# Inputs.net
KiCad netlist of a schematic drawn in Altium Designer
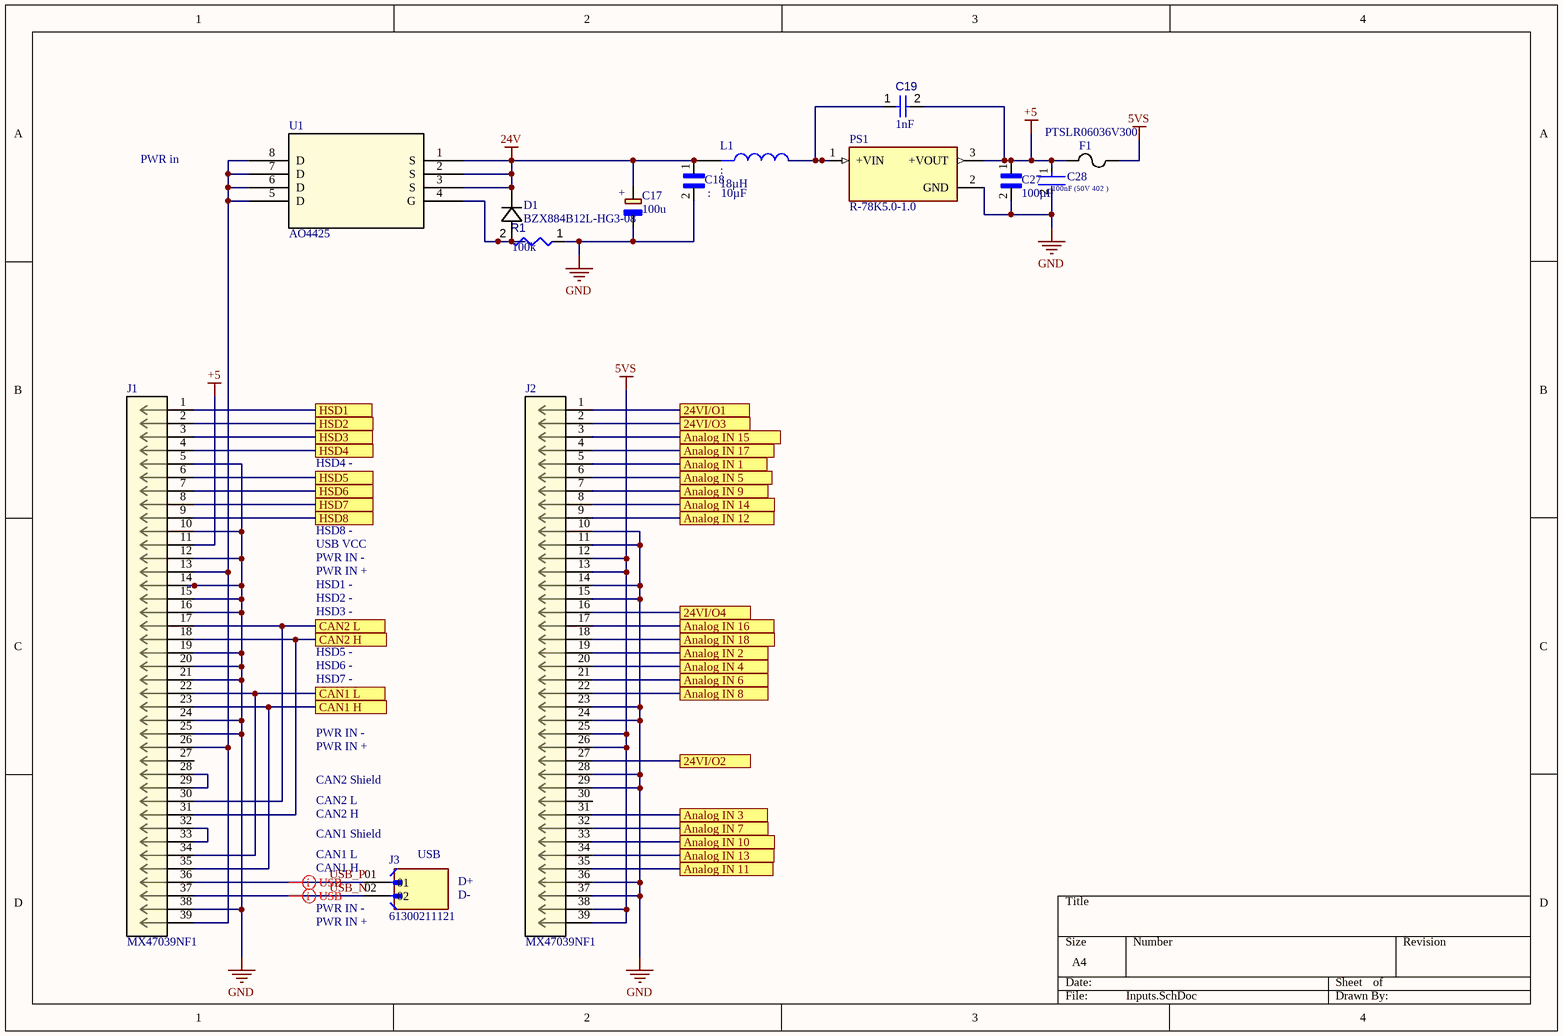
[diagram p0: Inputs.SchDoc]

(export (version "E")
  (design (tool "Eeschema 10.0.6"))
  (components
    (comp (ref "C17")
      (value "100u")
      (footprint "865080445010")
      (description "100 ÂµF 35 V Aluminum Electrolytic Capacitors Radial, Can - SMD - 2000 Hrs @ 105Â°C")
      (fields (field (name "MF") "WÃ¼rth Elektronik") (field (name "MP") "865080545012"))
      (libsource (lib "Western Formula Racing") (part "865080545012"))
    )
    (comp (ref "C18")
      (value "10µF")
      (footprint "CAPC2012X145N")
      (description "SMD capacitor X5R(EIA) with capacitance 10uF Tol.10%. Rated voltage 50Vdc 85C")
      (fields (field (name "MP") "GRM21BR61H106KE43L") (field (name "MF") "Murata Electronics"))
      (libsource (lib "Western Formula Racing") (part "GRM21BR61H106KE43L"))
    )
    (comp (ref "C19")
      (value "1nF")
      (footprint "CAPC0402(1005)33_L")
      (description "Chip Capacitor, 1nF +/-20%, 50V, 0402, Thickness 0.33 mm")
      (fields (field (name "TOLERANCE") "10%") (field (name "Comment") "Capacitor 1nF +/-20% 50V 0402"))
      (libsource (lib "Western Formula Racing") (part "CAP-NP-2"))
    )
    (comp (ref "C27")
      (value "100µF")
      (footprint "CAPC3216X190N")
      (fields (field (name "MP") "GRM31CR61A107MEA8L"))
      (libsource (lib "Western Formula Racing") (part "GRM31CR61A107MEA8L"))
    )
    (comp (ref "C28")
      (value "100nF (50V 402 )")
      (footprint "FP-CL779-IPC_C")
      (description "Cap Ceramic 100nF 50V X7R ±10% SMD 0402 +125°C Paper T/R")
      (libsource (lib "Altium Content Vault") (part "b4654b650e69147ec39a6b967a45e02"))
    )
    (comp (ref "D1")
      (value "BZX884B12L-HG3-08")
      (footprint "CR_9V1L-HG3-08_VIS")
      (description "No Description Available")
      (fields (field (name "COPYRIGHT") "Copyright (C) 2023 Ultra Librarian. All rights reserved."))
      (libsource (lib "Western Formula Racing") (part "BZX884B12L-HG3-08"))
    )
    (comp (ref "F1")
      (value "PTSLR06036V300")
      (footprint "FUSE_PTSLR06036V300_EAT")
      (description "No Description Available")
      (fields (field (name "COPYRIGHT") "Copyright (C) 2023 Ultra Librarian. All rights reserved."))
      (libsource (lib "Western Formula Racing") (part "PTSLR06036V300"))
    )
    (comp (ref "J1")
      (value "MX47039NF1")
      (footprint "CONN39_MX47039_JAE")
      (description "No Description Available")
      (fields (field (name "COPYRIGHT") "Copyright (C) 2023 Ultra Librarian. All rights reserved."))
      (libsource (lib "Western Formula Racing") (part "MX47039NF1"))
    )
    (comp (ref "J2")
      (value "MX47039NF1")
      (footprint "CONN39_MX47039_JAE")
      (description "No Description Available")
      (fields (field (name "COPYRIGHT") "Copyright (C) 2023 Ultra Librarian. All rights reserved."))
      (libsource (lib "Western Formula Racing") (part "MX47039NF1"))
    )
    (comp (ref "J3")
      (value "61300211121")
      (footprint "WURTH_61300211121")
      (description "Connector Header Through Hole 2 position 0.100 (2.54mm)")
      (fields (field (name "MF") "Wurth Electronics"))
      (libsource (lib "Western Formula Racing") (part "61300211121"))
    )
    (comp (ref "L1")
      (value "18µH")
      (footprint "IND_RLS-186")
      (description "Line Inductors for RECOM Power Supply")
      (fields (field (name "MP") "RLS-186") (field (name "MF") "Recom Power"))
      (libsource (lib "Western Formula Racing") (part "RLS-186"))
    )
    (comp (ref "PS1")
      (value "R-78K5.0-1.0")
      (footprint "CONV_R-78K5.0-1.0")
      (description "1A DC/DC-Converter 'INNOLINE' SIP3 reg")
      (fields (field (name "MF") "Recom Power"))
      (libsource (lib "Western Formula Racing") (part "R-78K5.0-1.0"))
    )
    (comp (ref "R1")
      (value "100k")
      (footprint "RESC0402(1005)_L")
      (description "Chip Resistor, 100 kOhms, +/-1 %, 63 mW, -55 to 155 degC, 0402")
      (fields (field (name "TOLERANCE") "1%") (field (name "POWER") "63mW"))
      (libsource (lib "Western Formula Racing") (part "RES-2"))
    )
    (comp (ref "U1")
      (value "AO4425")
      (footprint "SO-8_AOS")
      (description "No Description Available")
      (fields (field (name "COPYRIGHT") "Copyright (C) 2023 Ultra Librarian. All rights reserved."))
      (libsource (lib "Western Formula Racing") (part "AO4286"))
    )
  )
  (nets
    (net (code "1") (name "+5") (class "Default")
      (node (ref "C19") (pin "2") (pinfunction "2_2") (pintype "passive"))
      (node (ref "C27") (pin "1") (pinfunction "1_1") (pintype "passive"))
      (node (ref "C28") (pin "1") (pinfunction "1_1") (pintype "passive"))
      (node (ref "F1") (pin "1") (pinfunction "1_1") (pintype "passive"))
      (node (ref "J1") (pin "11") (pinfunction "11_11") (pintype "passive"))
      (node (ref "PS1") (pin "3") (pinfunction "+VOUT_3") (pintype "output"))
    )
    (net (code "2") (name "/24VI{slash}O1") (class "Default")
      (node (ref "J2") (pin "1") (pinfunction "1_1") (pintype "passive"))
    )
    (net (code "3") (name "/24VI{slash}O2") (class "Default")
      (node (ref "J2") (pin "27") (pinfunction "27_27") (pintype "passive"))
    )
    (net (code "4") (name "/24VI{slash}O3") (class "Default")
      (node (ref "J2") (pin "2") (pinfunction "2_2") (pintype "passive"))
    )
    (net (code "5") (name "/24VI{slash}O4") (class "Default")
      (node (ref "J2") (pin "16") (pinfunction "16_16") (pintype "passive"))
    )
    (net (code "6") (name "/Analog IN 1") (class "Default")
      (node (ref "J2") (pin "5") (pinfunction "5_5") (pintype "passive"))
    )
    (net (code "7") (name "/Analog IN 2") (class "Default")
      (node (ref "J2") (pin "19") (pinfunction "19_19") (pintype "passive"))
    )
    (net (code "8") (name "/Analog IN 3") (class "Default")
      (node (ref "J2") (pin "31") (pinfunction "31_31") (pintype "passive"))
    )
    (net (code "9") (name "/Analog IN 4") (class "Default")
      (node (ref "J2") (pin "20") (pinfunction "20_20") (pintype "passive"))
    )
    (net (code "10") (name "/Analog IN 5") (class "Default")
      (node (ref "J2") (pin "6") (pinfunction "6_6") (pintype "passive"))
    )
    (net (code "11") (name "/Analog IN 6") (class "Default")
      (node (ref "J2") (pin "21") (pinfunction "21_21") (pintype "passive"))
    )
    (net (code "12") (name "/Analog IN 7") (class "Default")
      (node (ref "J2") (pin "32") (pinfunction "32_32") (pintype "passive"))
    )
    (net (code "13") (name "/Analog IN 8") (class "Default")
      (node (ref "J2") (pin "22") (pinfunction "22_22") (pintype "passive"))
    )
    (net (code "14") (name "/Analog IN 9") (class "Default")
      (node (ref "J2") (pin "7") (pinfunction "7_7") (pintype "passive"))
    )
    (net (code "15") (name "/Analog IN 10") (class "Default")
      (node (ref "J2") (pin "33") (pinfunction "33_33") (pintype "passive"))
    )
    (net (code "16") (name "/Analog IN 11") (class "Default")
      (node (ref "J2") (pin "35") (pinfunction "35_35") (pintype "passive"))
    )
    (net (code "17") (name "/Analog IN 12") (class "Default")
      (node (ref "J2") (pin "9") (pinfunction "9_9") (pintype "passive"))
    )
    (net (code "18") (name "/Analog IN 13") (class "Default")
      (node (ref "J2") (pin "34") (pinfunction "34_34") (pintype "passive"))
    )
    (net (code "19") (name "/Analog IN 14") (class "Default")
      (node (ref "J2") (pin "8") (pinfunction "8_8") (pintype "passive"))
    )
    (net (code "20") (name "/Analog IN 15") (class "Default")
      (node (ref "J2") (pin "3") (pinfunction "3_3") (pintype "passive"))
    )
    (net (code "21") (name "/Analog IN 16") (class "Default")
      (node (ref "J2") (pin "17") (pinfunction "17_17") (pintype "passive"))
    )
    (net (code "22") (name "/Analog IN 17") (class "Default")
      (node (ref "J2") (pin "4") (pinfunction "4_4") (pintype "passive"))
    )
    (net (code "23") (name "/Analog IN 18") (class "Default")
      (node (ref "J2") (pin "18") (pinfunction "18_18") (pintype "passive"))
    )
    (net (code "24") (name "/CAN1 H") (class "Default")
      (node (ref "J1") (pin "23") (pinfunction "23_23") (pintype "passive"))
      (node (ref "J1") (pin "35") (pinfunction "35_35") (pintype "passive"))
    )
    (net (code "25") (name "/CAN1 L") (class "Default")
      (node (ref "J1") (pin "22") (pinfunction "22_22") (pintype "passive"))
      (node (ref "J1") (pin "34") (pinfunction "34_34") (pintype "passive"))
    )
    (net (code "26") (name "/CAN2 H") (class "Default")
      (node (ref "J1") (pin "18") (pinfunction "18_18") (pintype "passive"))
      (node (ref "J1") (pin "31") (pinfunction "31_31") (pintype "passive"))
    )
    (net (code "27") (name "/CAN2 L") (class "Default")
      (node (ref "J1") (pin "17") (pinfunction "17_17") (pintype "passive"))
      (node (ref "J1") (pin "30") (pinfunction "30_30") (pintype "passive"))
    )
    (net (code "28") (name "/HSD1") (class "Default")
      (node (ref "J1") (pin "1") (pinfunction "1_1") (pintype "passive"))
    )
    (net (code "29") (name "/HSD2") (class "Default")
      (node (ref "J1") (pin "2") (pinfunction "2_2") (pintype "passive"))
    )
    (net (code "30") (name "/HSD3") (class "Default")
      (node (ref "J1") (pin "3") (pinfunction "3_3") (pintype "passive"))
    )
    (net (code "31") (name "/HSD4") (class "Default")
      (node (ref "J1") (pin "4") (pinfunction "4_4") (pintype "passive"))
    )
    (net (code "32") (name "/HSD5") (class "Default")
      (node (ref "J1") (pin "6") (pinfunction "6_6") (pintype "passive"))
    )
    (net (code "33") (name "/HSD6") (class "Default")
      (node (ref "J1") (pin "7") (pinfunction "7_7") (pintype "passive"))
    )
    (net (code "34") (name "/HSD7") (class "Default")
      (node (ref "J1") (pin "8") (pinfunction "8_8") (pintype "passive"))
    )
    (net (code "35") (name "/HSD8") (class "Default")
      (node (ref "J1") (pin "9") (pinfunction "9_9") (pintype "passive"))
    )
    (net (code "36") (name "/USB_N") (class "Default")
      (node (ref "J1") (pin "37") (pinfunction "37_37") (pintype "passive"))
      (node (ref "J3") (pin "02") (pinfunction "02_02") (pintype "passive"))
    )
    (net (code "37") (name "/USB_P") (class "Default")
      (node (ref "J1") (pin "36") (pinfunction "36_36") (pintype "passive"))
      (node (ref "J3") (pin "01") (pinfunction "01_01") (pintype "passive"))
    )
    (net (code "38") (name "5VS") (class "Default")
      (node (ref "F1") (pin "2") (pinfunction "2_2") (pintype "passive"))
      (node (ref "J2") (pin "12") (pinfunction "12_12") (pintype "passive"))
      (node (ref "J2") (pin "13") (pinfunction "13_13") (pintype "passive"))
      (node (ref "J2") (pin "25") (pinfunction "25_25") (pintype "passive"))
      (node (ref "J2") (pin "26") (pinfunction "26_26") (pintype "passive"))
      (node (ref "J2") (pin "38") (pinfunction "38_38") (pintype "passive"))
      (node (ref "J2") (pin "39") (pinfunction "39_39") (pintype "passive"))
    )
    (net (code "39") (name "24V") (class "Default")
      (node (ref "C17") (pin "POS") (pinfunction "POS_POS") (pintype "passive"))
      (node (ref "C18") (pin "1") (pinfunction "1_1") (pintype "passive"))
      (node (ref "D1") (pin "1") (pinfunction "1_1") (pintype "passive"))
      (node (ref "L1") (pin "1") (pinfunction "1_1") (pintype "passive"))
      (node (ref "U1") (pin "1") (pinfunction "S_1") (pintype "passive"))
      (node (ref "U1") (pin "2") (pinfunction "S_2") (pintype "passive"))
      (node (ref "U1") (pin "3") (pinfunction "S_3") (pintype "passive"))
    )
    (net (code "40") (name "GND") (class "Default")
      (node (ref "C17") (pin "NEG") (pinfunction "NEG_NEG") (pintype "passive"))
      (node (ref "C18") (pin "2") (pinfunction "2_2") (pintype "passive"))
      (node (ref "C27") (pin "2") (pinfunction "2_2") (pintype "passive"))
      (node (ref "C28") (pin "2") (pinfunction "2_2") (pintype "passive"))
      (node (ref "J1") (pin "10") (pinfunction "10_10") (pintype "passive"))
      (node (ref "J1") (pin "12") (pinfunction "12_12") (pintype "passive"))
      (node (ref "J1") (pin "14") (pinfunction "14_14") (pintype "passive"))
      (node (ref "J1") (pin "15") (pinfunction "15_15") (pintype "passive"))
      (node (ref "J1") (pin "16") (pinfunction "16_16") (pintype "passive"))
      (node (ref "J1") (pin "19") (pinfunction "19_19") (pintype "passive"))
      (node (ref "J1") (pin "20") (pinfunction "20_20") (pintype "passive"))
      (node (ref "J1") (pin "21") (pinfunction "21_21") (pintype "passive"))
      (node (ref "J1") (pin "24") (pinfunction "24_24") (pintype "passive"))
      (node (ref "J1") (pin "25") (pinfunction "25_25") (pintype "passive"))
      (node (ref "J1") (pin "38") (pinfunction "38_38") (pintype "passive"))
      (node (ref "J1") (pin "5") (pinfunction "5_5") (pintype "passive"))
      (node (ref "J2") (pin "10") (pinfunction "10_10") (pintype "passive"))
      (node (ref "J2") (pin "11") (pinfunction "11_11") (pintype "passive"))
      (node (ref "J2") (pin "14") (pinfunction "14_14") (pintype "passive"))
      (node (ref "J2") (pin "15") (pinfunction "15_15") (pintype "passive"))
      (node (ref "J2") (pin "23") (pinfunction "23_23") (pintype "passive"))
      (node (ref "J2") (pin "24") (pinfunction "24_24") (pintype "passive"))
      (node (ref "J2") (pin "28") (pinfunction "28_28") (pintype "passive"))
      (node (ref "J2") (pin "29") (pinfunction "29_29") (pintype "passive"))
      (node (ref "J2") (pin "36") (pinfunction "36_36") (pintype "passive"))
      (node (ref "J2") (pin "37") (pinfunction "37_37") (pintype "passive"))
      (node (ref "PS1") (pin "2") (pinfunction "GND_2") (pintype "power_in"))
      (node (ref "R1") (pin "1") (pinfunction "1_1") (pintype "passive"))
    )
    (net (code "41") (name "Net-(J1-Pad13)") (class "Default")
      (node (ref "J1") (pin "13") (pinfunction "13_13") (pintype "passive"))
      (node (ref "J1") (pin "26") (pinfunction "26_26") (pintype "passive"))
      (node (ref "J1") (pin "39") (pinfunction "39_39") (pintype "passive"))
      (node (ref "U1") (pin "5") (pinfunction "D_5") (pintype "passive"))
      (node (ref "U1") (pin "6") (pinfunction "D_6") (pintype "passive"))
      (node (ref "U1") (pin "7") (pinfunction "D_7") (pintype "passive"))
      (node (ref "U1") (pin "8") (pinfunction "D_8") (pintype "passive"))
    )
    (net (code "42") (name "Net-(J1-Pad28)") (class "Default")
      (node (ref "J1") (pin "28") (pinfunction "28_28") (pintype "passive"))
      (node (ref "J1") (pin "29") (pinfunction "29_29") (pintype "passive"))
    )
    (net (code "43") (name "Net-(J1-Pad32)") (class "Default")
      (node (ref "J1") (pin "32") (pinfunction "32_32") (pintype "passive"))
      (node (ref "J1") (pin "33") (pinfunction "33_33") (pintype "passive"))
    )
    (net (code "44") (name "Net-(PS1-+VIN)") (class "Default")
      (node (ref "C19") (pin "1") (pinfunction "1_1") (pintype "passive"))
      (node (ref "L1") (pin "2") (pinfunction "2_2") (pintype "passive"))
      (node (ref "PS1") (pin "1") (pinfunction "+VIN_1") (pintype "input"))
    )
    (net (code "45") (name "Net-(U1-G)") (class "Default")
      (node (ref "D1") (pin "2") (pinfunction "2_2") (pintype "passive"))
      (node (ref "R1") (pin "2") (pinfunction "2_2") (pintype "passive"))
      (node (ref "U1") (pin "4") (pinfunction "G_4") (pintype "passive"))
    )
    (net (code "46") (name "unconnected-(J1-Pad27)") (class "Default")
      (node (ref "J1") (pin "27") (pinfunction "27_27") (pintype "passive"))
    )
    (net (code "47") (name "unconnected-(J2-Pad30)") (class "Default")
      (node (ref "J2") (pin "30") (pinfunction "30_30") (pintype "passive"))
    )
  )
)
